# RADC-Connectors-S01-V00.net
KiCad netlist of a schematic drawn in Altium Designer
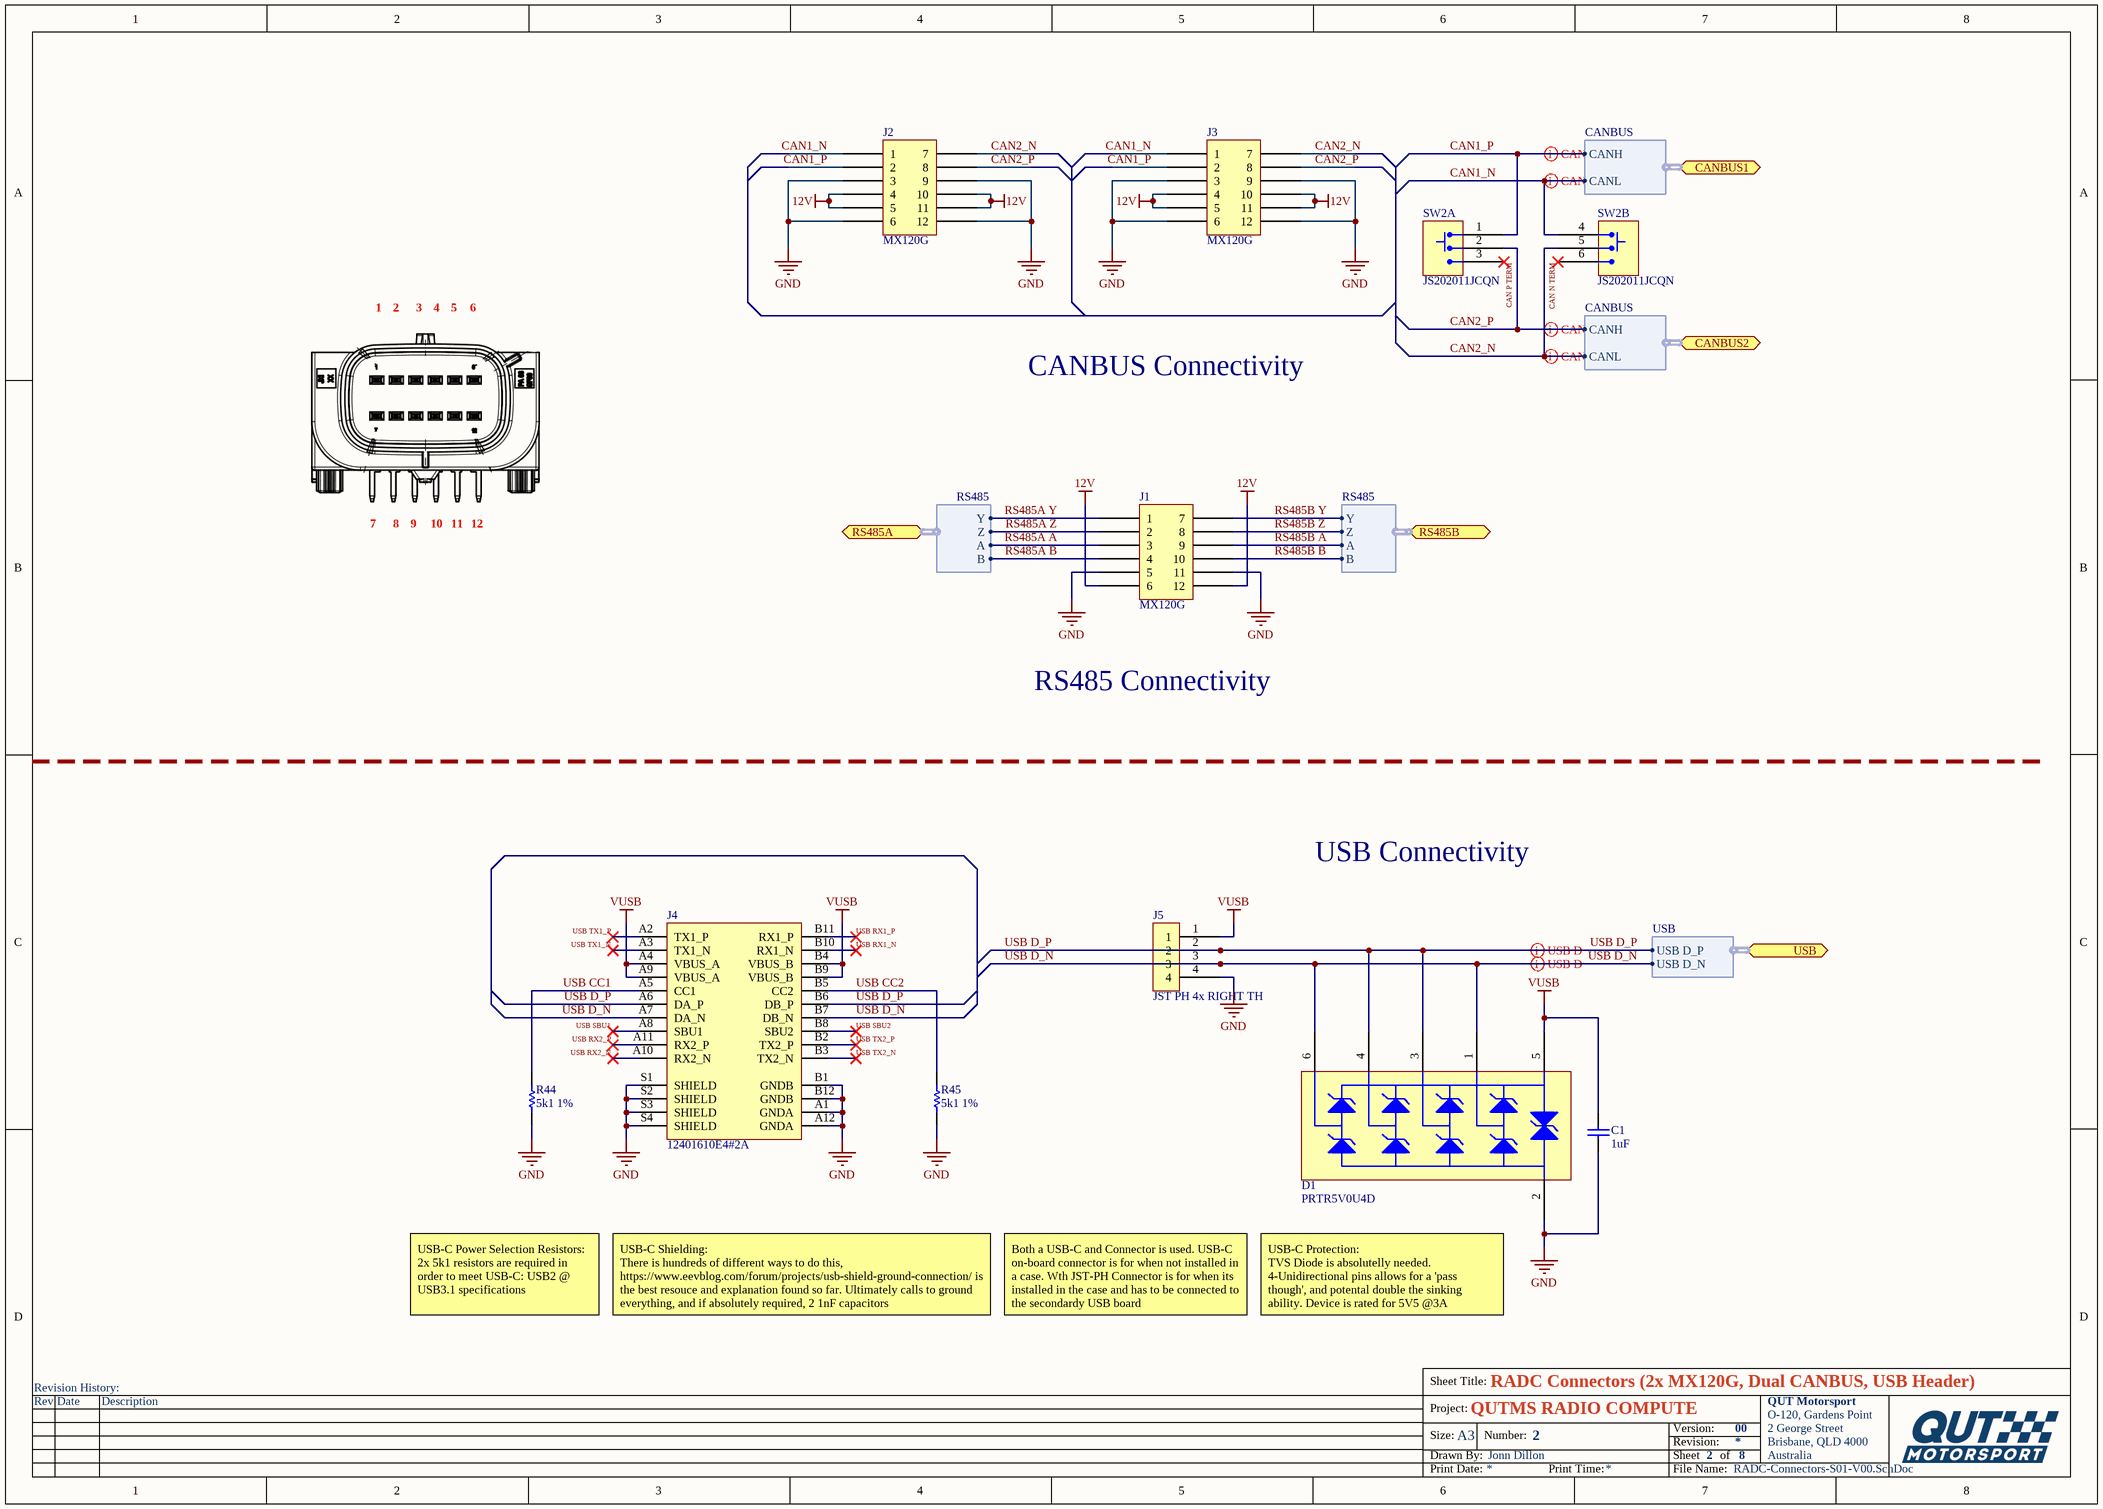
[diagram p0: RADC-Connectors-S01-V00.SchDoc]

(export (version "E")
  (design (tool "Eeschema 10.0.6"))
  (components
    (comp (ref "C1")
      (value "1uF")
      (footprint "Cap_Ceramic_0603")
      (description "Capacitor, Ceramic, SMD, 1uF, 25V, 5%, X7R, 0603")
      (libsource (lib "StandardCapacitors") (part "1uF 25V 5% X7R 0603"))
    )
    (comp (ref "D1")
      (value "PRTR5V0U4D")
      (footprint "SC-47")
      (description "Clamp Ipp Tvs Diode Surface Mount 6-TSOP")
      (libsource (lib "QUTMS_DiodeLibrary") (part "PRTR5V0U4D"))
    )
    (comp (ref "J1")
      (value "MX120G")
      (footprint "MX120G")
      (description "MX120G with standard connector layout")
      (libsource (lib "QUTMS_MolexLibrary") (part "MX120G"))
    )
    (comp (ref "J2")
      (value "MX120G")
      (footprint "MX120G")
      (description "MX120G with standard connector layout")
      (libsource (lib "QUTMS_MolexLibrary") (part "MX120G"))
    )
    (comp (ref "J3")
      (value "MX120G")
      (footprint "MX120G")
      (description "MX120G with standard connector layout")
      (libsource (lib "QUTMS_MolexLibrary") (part "MX120G"))
    )
    (comp (ref "J4")
      (value "12401610E4#2A")
      (footprint "12401610E4#2A")
      (libsource (lib "QUTMS_USBLibrary") (part "12401610E4#2A"))
    )
    (comp (ref "J5")
      (value "JST PH 4x RIGHT TH")
      (footprint "JST PH 4x RIGHT TH")
      (libsource (lib "QUTMS_JST_PH") (part "JST PH 4x RIGHT TH"))
    )
    (comp (ref "R44")
      (value "5k1 1%")
      (footprint "Res_ThinFilm_0603")
      (description "Resistor, SMD, 5k1, 0.1W, 1%, 0603")
      (libsource (lib "StandardResistors") (part "5k1 1% 0603"))
    )
    (comp (ref "R45")
      (value "5k1 1%")
      (footprint "Res_ThinFilm_0603")
      (description "Resistor, SMD, 5k1, 0.1W, 1%, 0603")
      (libsource (lib "StandardResistors") (part "5k1 1% 0603"))
    )
    (comp (ref "SW2")
      (value "JS202011JCQN")
      (footprint "JS202011JCQN")
      (libsource (lib "") (part "SLIDE DPDT JS202011JCQN_1"))
    )
  )
  (nets
    (net (code "4") (name "/CAN N TERM") (class "Default")
      (node (ref "SW2") (pin "6") (pinfunction "6_6") (pintype "passive+no_connect"))
    )
    (net (code "5") (name "/CAN P TERM") (class "Default")
      (node (ref "SW2") (pin "3") (pinfunction "3_3") (pintype "passive+no_connect"))
    )
    (net (code "6") (name "/CAN1_N") (class "Default")
      (node (ref "J2") (pin "1") (pinfunction "1_1") (pintype "passive"))
      (node (ref "J3") (pin "1") (pinfunction "1_1") (pintype "passive"))
      (node (ref "SW2") (pin "4") (pinfunction "4_4") (pintype "passive"))
    )
    (net (code "7") (name "/CAN1_P") (class "Default")
      (node (ref "J2") (pin "2") (pinfunction "2_2") (pintype "passive"))
      (node (ref "J3") (pin "2") (pinfunction "2_2") (pintype "passive"))
      (node (ref "SW2") (pin "1") (pinfunction "1_1") (pintype "passive"))
    )
    (net (code "8") (name "/CAN2_N") (class "Default")
      (node (ref "J2") (pin "7") (pinfunction "7_7") (pintype "passive"))
      (node (ref "J3") (pin "7") (pinfunction "7_7") (pintype "passive"))
      (node (ref "SW2") (pin "5") (pinfunction "5_5") (pintype "passive"))
    )
    (net (code "9") (name "/CAN2_P") (class "Default")
      (node (ref "J2") (pin "8") (pinfunction "8_8") (pintype "passive"))
      (node (ref "J3") (pin "8") (pinfunction "8_8") (pintype "passive"))
      (node (ref "SW2") (pin "2") (pinfunction "2_2") (pintype "passive"))
    )
    (net (code "10") (name "/RS485A A") (class "Default")
      (node (ref "J1") (pin "3") (pinfunction "3_3") (pintype "passive"))
    )
    (net (code "11") (name "/RS485A B") (class "Default")
      (node (ref "J1") (pin "4") (pinfunction "4_4") (pintype "passive"))
    )
    (net (code "12") (name "/RS485A Y") (class "Default")
      (node (ref "J1") (pin "1") (pinfunction "1_1") (pintype "passive"))
    )
    (net (code "13") (name "/RS485A Z") (class "Default")
      (node (ref "J1") (pin "2") (pinfunction "2_2") (pintype "passive"))
    )
    (net (code "14") (name "/RS485B A") (class "Default")
      (node (ref "J1") (pin "9") (pinfunction "9_9") (pintype "passive"))
    )
    (net (code "15") (name "/RS485B B") (class "Default")
      (node (ref "J1") (pin "10") (pinfunction "10_10") (pintype "passive"))
    )
    (net (code "16") (name "/RS485B Y") (class "Default")
      (node (ref "J1") (pin "7") (pinfunction "7_7") (pintype "passive"))
    )
    (net (code "17") (name "/RS485B Z") (class "Default")
      (node (ref "J1") (pin "8") (pinfunction "8_8") (pintype "passive"))
    )
    (net (code "18") (name "/USB CC1") (class "Default")
      (node (ref "J4") (pin "A5") (pinfunction "CC1_A5") (pintype "passive"))
      (node (ref "R44") (pin "2") (pinfunction "2_2") (pintype "passive"))
    )
    (net (code "19") (name "/USB CC2") (class "Default")
      (node (ref "J4") (pin "B5") (pinfunction "CC2_B5") (pintype "passive"))
      (node (ref "R45") (pin "2") (pinfunction "2_2") (pintype "passive"))
    )
    (net (code "20") (name "/USB D_N") (class "Default")
      (node (ref "D1") (pin "1") (pinfunction "P1_1") (pintype "passive"))
      (node (ref "D1") (pin "6") (pinfunction "P4_6") (pintype "passive"))
      (node (ref "J4") (pin "A7") (pinfunction "DA_N_A7") (pintype "passive"))
      (node (ref "J4") (pin "B7") (pinfunction "DB_N_B7") (pintype "passive"))
      (node (ref "J5") (pin "3") (pinfunction "3_3") (pintype "passive"))
    )
    (net (code "21") (name "/USB D_P") (class "Default")
      (node (ref "D1") (pin "3") (pinfunction "P2_3") (pintype "passive"))
      (node (ref "D1") (pin "4") (pinfunction "P3_4") (pintype "passive"))
      (node (ref "J4") (pin "A6") (pinfunction "DA_P_A6") (pintype "passive"))
      (node (ref "J4") (pin "B6") (pinfunction "DB_P_B6") (pintype "passive"))
      (node (ref "J5") (pin "2") (pinfunction "2_2") (pintype "passive"))
    )
    (net (code "22") (name "/USB RX1_N") (class "Default")
      (node (ref "J4") (pin "B10") (pinfunction "RX1_N_B10") (pintype "passive+no_connect"))
    )
    (net (code "23") (name "/USB RX1_P") (class "Default")
      (node (ref "J4") (pin "B11") (pinfunction "RX1_P_B11") (pintype "passive+no_connect"))
    )
    (net (code "24") (name "/USB RX2_N") (class "Default")
      (node (ref "J4") (pin "A10") (pinfunction "RX2_N_A10") (pintype "passive+no_connect"))
    )
    (net (code "25") (name "/USB RX2_P") (class "Default")
      (node (ref "J4") (pin "A11") (pinfunction "RX2_P_A11") (pintype "passive+no_connect"))
    )
    (net (code "26") (name "/USB SBU1") (class "Default")
      (node (ref "J4") (pin "A8") (pinfunction "SBU1_A8") (pintype "passive+no_connect"))
    )
    (net (code "27") (name "/USB SBU2") (class "Default")
      (node (ref "J4") (pin "B8") (pinfunction "SBU2_B8") (pintype "passive+no_connect"))
    )
    (net (code "28") (name "/USB TX1_N") (class "Default")
      (node (ref "J4") (pin "A3") (pinfunction "TX1_N_A3") (pintype "passive+no_connect"))
    )
    (net (code "29") (name "/USB TX1_P") (class "Default")
      (node (ref "J4") (pin "A2") (pinfunction "TX1_P_A2") (pintype "passive+no_connect"))
    )
    (net (code "30") (name "/USB TX2_N") (class "Default")
      (node (ref "J4") (pin "B3") (pinfunction "TX2_N_B3") (pintype "passive+no_connect"))
    )
    (net (code "31") (name "/USB TX2_P") (class "Default")
      (node (ref "J4") (pin "B2") (pinfunction "TX2_P_B2") (pintype "passive+no_connect"))
    )
    (net (code "35") (name "12V") (class "Default")
      (node (ref "J1") (pin "12") (pinfunction "12_12") (pintype "passive"))
      (node (ref "J1") (pin "6") (pinfunction "6_6") (pintype "passive"))
      (node (ref "J2") (pin "10") (pinfunction "10_10") (pintype "passive"))
      (node (ref "J2") (pin "11") (pinfunction "11_11") (pintype "passive"))
      (node (ref "J2") (pin "4") (pinfunction "4_4") (pintype "passive"))
      (node (ref "J2") (pin "5") (pinfunction "5_5") (pintype "passive"))
      (node (ref "J3") (pin "10") (pinfunction "10_10") (pintype "passive"))
      (node (ref "J3") (pin "11") (pinfunction "11_11") (pintype "passive"))
      (node (ref "J3") (pin "4") (pinfunction "4_4") (pintype "passive"))
      (node (ref "J3") (pin "5") (pinfunction "5_5") (pintype "passive"))
    )
    (net (code "36") (name "GND") (class "Default")
      (node (ref "C1") (pin "1") (pinfunction "1_1") (pintype "passive"))
      (node (ref "D1") (pin "2") (pinfunction "GND_2") (pintype "passive"))
      (node (ref "J1") (pin "11") (pinfunction "11_11") (pintype "passive"))
      (node (ref "J1") (pin "5") (pinfunction "5_5") (pintype "passive"))
      (node (ref "J2") (pin "12") (pinfunction "12_12") (pintype "passive"))
      (node (ref "J2") (pin "3") (pinfunction "3_3") (pintype "passive"))
      (node (ref "J2") (pin "6") (pinfunction "6_6") (pintype "passive"))
      (node (ref "J2") (pin "9") (pinfunction "9_9") (pintype "passive"))
      (node (ref "J3") (pin "12") (pinfunction "12_12") (pintype "passive"))
      (node (ref "J3") (pin "3") (pinfunction "3_3") (pintype "passive"))
      (node (ref "J3") (pin "6") (pinfunction "6_6") (pintype "passive"))
      (node (ref "J3") (pin "9") (pinfunction "9_9") (pintype "passive"))
      (node (ref "J4") (pin "A1") (pinfunction "GNDA_A1") (pintype "passive"))
      (node (ref "J4") (pin "A12") (pinfunction "GNDA_A12") (pintype "passive"))
      (node (ref "J4") (pin "B1") (pinfunction "GNDB_B1") (pintype "passive"))
      (node (ref "J4") (pin "B12") (pinfunction "GNDB_B12") (pintype "passive"))
      (node (ref "J4") (pin "S1") (pinfunction "SHIELD_S1") (pintype "power_in"))
      (node (ref "J4") (pin "S2") (pinfunction "SHIELD_S2") (pintype "power_in"))
      (node (ref "J4") (pin "S3") (pinfunction "SHIELD_S3") (pintype "power_in"))
      (node (ref "J4") (pin "S4") (pinfunction "SHIELD_S4") (pintype "power_in"))
      (node (ref "J5") (pin "4") (pinfunction "4_4") (pintype "passive"))
      (node (ref "R44") (pin "1") (pinfunction "1_1") (pintype "passive"))
      (node (ref "R45") (pin "1") (pinfunction "1_1") (pintype "passive"))
    )
    (net (code "37") (name "VUSB") (class "Default")
      (node (ref "C1") (pin "2") (pinfunction "2_2") (pintype "passive"))
      (node (ref "D1") (pin "5") (pinfunction "VCC_5") (pintype "passive"))
      (node (ref "J4") (pin "A4") (pinfunction "VBUS_A_A4") (pintype "passive"))
      (node (ref "J4") (pin "A9") (pinfunction "VBUS_A_A9") (pintype "passive"))
      (node (ref "J4") (pin "B4") (pinfunction "VBUS_B_B4") (pintype "passive"))
      (node (ref "J4") (pin "B9") (pinfunction "VBUS_B_B9") (pintype "passive"))
      (node (ref "J5") (pin "1") (pinfunction "1_1") (pintype "passive"))
    )
  )
)
